# M220X.net
KiCad netlist of a schematic drawn in EAGLE
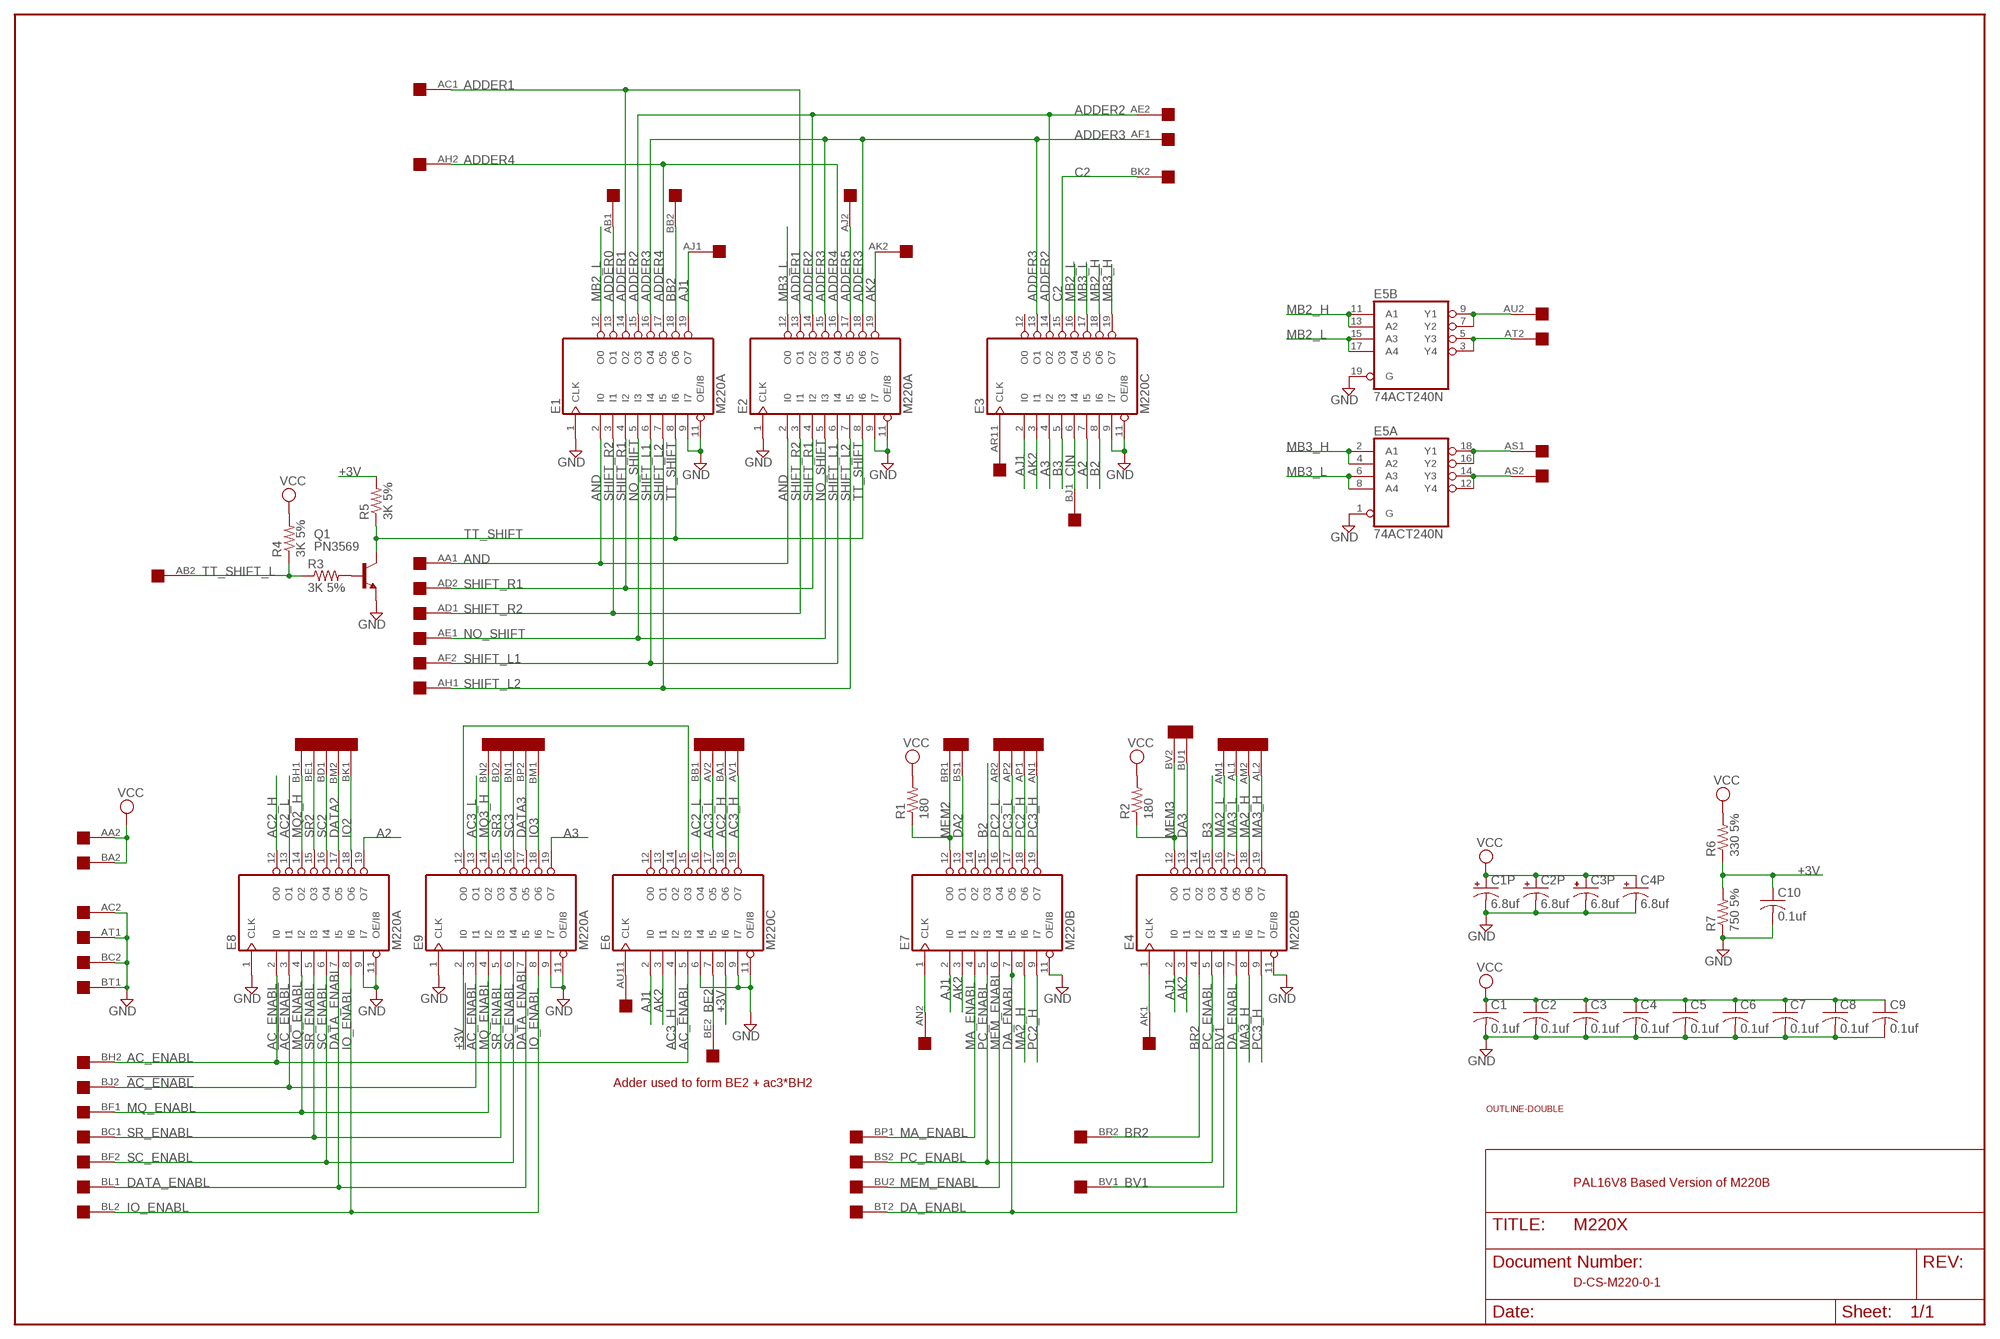
[diagram p0: schematic, sheet 1]

(export (version "E")
  (design (tool "Eeschema 10.0.6"))
  (components
    (comp (ref "C1")
      (value "0.1uf")
      (footprint "eagle-import:C050-025X075")
      (libsource (lib "eagle-import") (part "C-US050-025X075"))
    )
    (comp (ref "C1P")
      (value "6.8uf")
      (footprint "eagle-import:E15-5")
      (libsource (lib "eagle-import") (part "CPOL-USE15-5AXIAL"))
    )
    (comp (ref "C2")
      (value "0.1uf")
      (footprint "eagle-import:C050-025X075")
      (libsource (lib "eagle-import") (part "C-US050-025X075"))
    )
    (comp (ref "C2P")
      (value "6.8uf")
      (footprint "eagle-import:E15-5")
      (libsource (lib "eagle-import") (part "CPOL-USE15-5AXIAL"))
    )
    (comp (ref "C3")
      (value "0.1uf")
      (footprint "eagle-import:C050-025X075")
      (libsource (lib "eagle-import") (part "C-US050-025X075"))
    )
    (comp (ref "C3P")
      (value "6.8uf")
      (footprint "eagle-import:E15-5")
      (libsource (lib "eagle-import") (part "CPOL-USE15-5AXIAL"))
    )
    (comp (ref "C4")
      (value "0.1uf")
      (footprint "eagle-import:C050-025X075")
      (libsource (lib "eagle-import") (part "C-US050-025X075"))
    )
    (comp (ref "C4P")
      (value "6.8uf")
      (footprint "eagle-import:E15-5")
      (libsource (lib "eagle-import") (part "CPOL-USE15-5AXIAL"))
    )
    (comp (ref "C5")
      (value "0.1uf")
      (footprint "eagle-import:C050-025X075")
      (libsource (lib "eagle-import") (part "C-US050-025X075"))
    )
    (comp (ref "C6")
      (value "0.1uf")
      (footprint "eagle-import:C050-025X075")
      (libsource (lib "eagle-import") (part "C-US050-025X075"))
    )
    (comp (ref "C7")
      (value "0.1uf")
      (footprint "eagle-import:C050-025X075")
      (libsource (lib "eagle-import") (part "C-US050-025X075"))
    )
    (comp (ref "C8")
      (value "0.1uf")
      (footprint "eagle-import:C050-025X075")
      (libsource (lib "eagle-import") (part "C-US050-025X075"))
    )
    (comp (ref "C9")
      (value "0.1uf")
      (footprint "eagle-import:C050-025X075")
      (libsource (lib "eagle-import") (part "C-US050-025X075"))
    )
    (comp (ref "C10")
      (value "0.1uf")
      (footprint "eagle-import:C050-025X075")
      (libsource (lib "eagle-import") (part "C-US050-025X075"))
    )
    (comp (ref "E1")
      (value "M220A")
      (footprint "eagle-import:DIL20")
      (fields (field (name "MPN") "GAL16V8D-7LPN"))
      (libsource (lib "eagle-import") (part "16V8"))
    )
    (comp (ref "E2")
      (value "M220A")
      (footprint "eagle-import:DIL20")
      (fields (field (name "MPN") "GAL16V8D-7LPN"))
      (libsource (lib "eagle-import") (part "16V8"))
    )
    (comp (ref "E3")
      (value "M220C")
      (footprint "eagle-import:DIL20")
      (fields (field (name "MPN") "GAL16V8D-7LPN"))
      (libsource (lib "eagle-import") (part "16V8"))
    )
    (comp (ref "E4")
      (value "M220B")
      (footprint "eagle-import:DIL20")
      (fields (field (name "MPN") "GAL16V8D-7LPN"))
      (libsource (lib "eagle-import") (part "16V8"))
    )
    (comp (ref "E5")
      (value "74ACT240N")
      (footprint "eagle-import:DIL20")
      (libsource (lib "eagle-import") (part "74240NS"))
    )
    (comp (ref "E6")
      (value "M220C")
      (footprint "eagle-import:DIL20")
      (fields (field (name "MPN") "GAL16V8D-7LPN"))
      (libsource (lib "eagle-import") (part "16V8"))
    )
    (comp (ref "E7")
      (value "M220B")
      (footprint "eagle-import:DIL20")
      (fields (field (name "MPN") "GAL16V8D-7LPN"))
      (libsource (lib "eagle-import") (part "16V8"))
    )
    (comp (ref "E8")
      (value "M220A")
      (footprint "eagle-import:DIL20")
      (fields (field (name "MPN") "GAL16V8D-7LPN"))
      (libsource (lib "eagle-import") (part "16V8"))
    )
    (comp (ref "E9")
      (value "M220A")
      (footprint "eagle-import:DIL20")
      (fields (field (name "MPN") "GAL16V8D-7LPN"))
      (libsource (lib "eagle-import") (part "16V8"))
    )
    (comp (ref "Q1")
      (value "PN3569")
      (footprint "eagle-import:TO5")
      (libsource (lib "eagle-import") (part "2N2102"))
    )
    (comp (ref "R1")
      (value "180")
      (footprint "eagle-import:0207_10")
      (libsource (lib "eagle-import") (part "R-US_0207/10"))
    )
    (comp (ref "R2")
      (value "180")
      (footprint "eagle-import:0207_10")
      (libsource (lib "eagle-import") (part "R-US_0207/10"))
    )
    (comp (ref "R3")
      (value "3K 5%")
      (footprint "eagle-import:0207_10")
      (libsource (lib "eagle-import") (part "R-US_0207/10"))
    )
    (comp (ref "R4")
      (value "3K 5%")
      (footprint "eagle-import:0207_10")
      (libsource (lib "eagle-import") (part "R-US_0207/10"))
    )
    (comp (ref "R5")
      (value "3K 5%")
      (footprint "eagle-import:0207_10")
      (libsource (lib "eagle-import") (part "R-US_0207/10"))
    )
    (comp (ref "R6")
      (value "330 5%")
      (footprint "eagle-import:0207_10")
      (libsource (lib "eagle-import") (part "R-US_0207/10"))
    )
    (comp (ref "R7")
      (value "750 5%")
      (footprint "eagle-import:0207_10")
      (libsource (lib "eagle-import") (part "R-US_0207/10"))
    )
    (comp (ref "U$1")
      (value "DOUBLE")
      (footprint "eagle-import:EDGE-CON4")
      (libsource (lib "eagle-import") (part "DOUBLE"))
    )
    (comp (ref "U$2")
      (value "OUTLINE-DOUBLE")
      (footprint "eagle-import:DOUBLE")
      (libsource (lib "eagle-import") (part "OUTLINE-DOUBLE"))
    )
  )
  (nets
    (net (code "1") (name "/+3V") (class "Default")
      (node (ref "C10") (pin "1") (pinfunction "1_1") (pintype "passive"))
      (node (ref "E6") (pin "8") (pinfunction "I6_8") (pintype "input"))
      (node (ref "E9") (pin "2") (pinfunction "I0_2") (pintype "input"))
      (node (ref "R5") (pin "2") (pinfunction "2_2") (pintype "passive"))
      (node (ref "R6") (pin "1") (pinfunction "1_1") (pintype "passive"))
      (node (ref "R7") (pin "2") (pinfunction "2_2") (pintype "passive"))
    )
    (net (code "2") (name "/A2") (class "Default")
      (node (ref "E3") (pin "7") (pinfunction "I5_7") (pintype "input"))
      (node (ref "E8") (pin "19") (pinfunction "O7_19") (pintype "bidirectional"))
    )
    (net (code "3") (name "/A3") (class "Default")
      (node (ref "E3") (pin "4") (pinfunction "I2_4") (pintype "input"))
      (node (ref "E9") (pin "19") (pinfunction "O7_19") (pintype "bidirectional"))
    )
    (net (code "4") (name "/AC2_H") (class "Default")
      (node (ref "E6") (pin "18") (pinfunction "O6_18") (pintype "bidirectional"))
      (node (ref "E8") (pin "12") (pinfunction "O0_12") (pintype "bidirectional"))
      (node (ref "U$1") (pin "BA1") (pinfunction "1_BA1") (pintype "bidirectional"))
    )
    (net (code "5") (name "/AC2_L") (class "Default")
      (node (ref "E6") (pin "16") (pinfunction "O4_16") (pintype "bidirectional"))
      (node (ref "E8") (pin "13") (pinfunction "O1_13") (pintype "bidirectional"))
      (node (ref "U$1") (pin "BB1") (pinfunction "1_BB1") (pintype "bidirectional"))
    )
    (net (code "6") (name "/AC3_H") (class "Default")
      (node (ref "E6") (pin "19") (pinfunction "O7_19") (pintype "bidirectional"))
      (node (ref "E6") (pin "4") (pinfunction "I2_4") (pintype "input"))
      (node (ref "U$1") (pin "AV1") (pinfunction "1_AV1") (pintype "bidirectional"))
    )
    (net (code "7") (name "/AC3_L") (class "Default")
      (node (ref "E6") (pin "17") (pinfunction "O5_17") (pintype "bidirectional"))
      (node (ref "E9") (pin "13") (pinfunction "O1_13") (pintype "bidirectional"))
      (node (ref "U$1") (pin "AV2") (pinfunction "1_AV2") (pintype "bidirectional"))
    )
    (net (code "8") (name "/AC_ENABL") (class "Default")
      (node (ref "E6") (pin "5") (pinfunction "I3_5") (pintype "input"))
      (node (ref "E8") (pin "2") (pinfunction "I0_2") (pintype "input"))
      (node (ref "U$1") (pin "BH2") (pinfunction "1_BH2") (pintype "bidirectional"))
    )
    (net (code "9") (name "/ADDER0") (class "Default")
      (node (ref "E1") (pin "13") (pinfunction "O1_13") (pintype "bidirectional"))
      (node (ref "U$1") (pin "AB1") (pinfunction "1_AB1") (pintype "bidirectional"))
    )
    (net (code "10") (name "/ADDER1") (class "Default")
      (node (ref "E1") (pin "14") (pinfunction "O2_14") (pintype "bidirectional"))
      (node (ref "E2") (pin "13") (pinfunction "O1_13") (pintype "bidirectional"))
      (node (ref "U$1") (pin "AC1") (pinfunction "1_AC1") (pintype "bidirectional"))
    )
    (net (code "11") (name "/ADDER2") (class "Default")
      (node (ref "E1") (pin "15") (pinfunction "O3_15") (pintype "bidirectional"))
      (node (ref "E2") (pin "14") (pinfunction "O2_14") (pintype "bidirectional"))
      (node (ref "E3") (pin "14") (pinfunction "O2_14") (pintype "bidirectional"))
      (node (ref "U$1") (pin "AE2") (pinfunction "1_AE2") (pintype "bidirectional"))
    )
    (net (code "12") (name "/ADDER3") (class "Default")
      (node (ref "E1") (pin "16") (pinfunction "O4_16") (pintype "bidirectional"))
      (node (ref "E2") (pin "15") (pinfunction "O3_15") (pintype "bidirectional"))
      (node (ref "E2") (pin "18") (pinfunction "O6_18") (pintype "bidirectional"))
      (node (ref "E3") (pin "13") (pinfunction "O1_13") (pintype "bidirectional"))
      (node (ref "U$1") (pin "AF1") (pinfunction "1_AF1") (pintype "bidirectional"))
    )
    (net (code "13") (name "/ADDER4") (class "Default")
      (node (ref "E1") (pin "17") (pinfunction "O5_17") (pintype "bidirectional"))
      (node (ref "E2") (pin "16") (pinfunction "O4_16") (pintype "bidirectional"))
      (node (ref "U$1") (pin "AH2") (pinfunction "1_AH2") (pintype "bidirectional"))
    )
    (net (code "14") (name "/ADDER5") (class "Default")
      (node (ref "E2") (pin "17") (pinfunction "O5_17") (pintype "bidirectional"))
      (node (ref "U$1") (pin "AJ2") (pinfunction "1_AJ2") (pintype "bidirectional"))
    )
    (net (code "15") (name "/AJ1") (class "Default")
      (node (ref "E1") (pin "19") (pinfunction "O7_19") (pintype "bidirectional"))
      (node (ref "E3") (pin "2") (pinfunction "I0_2") (pintype "input"))
      (node (ref "E4") (pin "2") (pinfunction "I0_2") (pintype "input"))
      (node (ref "E6") (pin "2") (pinfunction "I0_2") (pintype "input"))
      (node (ref "E7") (pin "2") (pinfunction "I0_2") (pintype "input"))
      (node (ref "U$1") (pin "AJ1") (pinfunction "1_AJ1") (pintype "bidirectional"))
    )
    (net (code "16") (name "/AK2") (class "Default")
      (node (ref "E2") (pin "19") (pinfunction "O7_19") (pintype "bidirectional"))
      (node (ref "E3") (pin "3") (pinfunction "I1_3") (pintype "input"))
      (node (ref "E4") (pin "3") (pinfunction "I1_3") (pintype "input"))
      (node (ref "E6") (pin "3") (pinfunction "I1_3") (pintype "input"))
      (node (ref "E7") (pin "3") (pinfunction "I1_3") (pintype "input"))
      (node (ref "U$1") (pin "AK2") (pinfunction "1_AK2") (pintype "bidirectional"))
    )
    (net (code "17") (name "/AND") (class "Default")
      (node (ref "E1") (pin "2") (pinfunction "I0_2") (pintype "input"))
      (node (ref "E2") (pin "2") (pinfunction "I0_2") (pintype "input"))
      (node (ref "U$1") (pin "AA1") (pinfunction "1_AA1") (pintype "bidirectional"))
    )
    (net (code "18") (name "/B2") (class "Default")
      (node (ref "E3") (pin "8") (pinfunction "I6_8") (pintype "input"))
      (node (ref "E7") (pin "15") (pinfunction "O3_15") (pintype "bidirectional"))
    )
    (net (code "19") (name "/B3") (class "Default")
      (node (ref "E3") (pin "5") (pinfunction "I3_5") (pintype "input"))
      (node (ref "E4") (pin "15") (pinfunction "O3_15") (pintype "bidirectional"))
    )
    (net (code "20") (name "/BB2") (class "Default")
      (node (ref "E1") (pin "18") (pinfunction "O6_18") (pintype "bidirectional"))
      (node (ref "U$1") (pin "BB2") (pinfunction "1_BB2") (pintype "bidirectional"))
    )
    (net (code "21") (name "/BE2") (class "Default")
      (node (ref "E6") (pin "7") (pinfunction "I5_7") (pintype "input"))
      (node (ref "U$1") (pin "BE2") (pinfunction "1_BE2") (pintype "bidirectional"))
    )
    (net (code "22") (name "/BR2") (class "Default")
      (node (ref "E4") (pin "4") (pinfunction "I2_4") (pintype "input"))
      (node (ref "U$1") (pin "BR2") (pinfunction "1_BR2") (pintype "bidirectional"))
    )
    (net (code "23") (name "/BV1") (class "Default")
      (node (ref "E4") (pin "6") (pinfunction "I4_6") (pintype "input"))
      (node (ref "U$1") (pin "BV1") (pinfunction "1_BV1") (pintype "bidirectional"))
    )
    (net (code "24") (name "/C2") (class "Default")
      (node (ref "E3") (pin "15") (pinfunction "O3_15") (pintype "bidirectional"))
      (node (ref "U$1") (pin "BK2") (pinfunction "1_BK2") (pintype "bidirectional"))
    )
    (net (code "25") (name "/CIN") (class "Default")
      (node (ref "E3") (pin "6") (pinfunction "I4_6") (pintype "input"))
      (node (ref "U$1") (pin "BJ1") (pinfunction "1_BJ1") (pintype "bidirectional"))
    )
    (net (code "26") (name "/DA2") (class "Default")
      (node (ref "E7") (pin "13") (pinfunction "O1_13") (pintype "bidirectional"))
      (node (ref "U$1") (pin "BS1") (pinfunction "1_BS1") (pintype "bidirectional"))
    )
    (net (code "27") (name "/DA3") (class "Default")
      (node (ref "E4") (pin "13") (pinfunction "O1_13") (pintype "bidirectional"))
      (node (ref "U$1") (pin "BU1") (pinfunction "1_BU1") (pintype "bidirectional"))
    )
    (net (code "28") (name "/DATA2") (class "Default")
      (node (ref "E8") (pin "17") (pinfunction "O5_17") (pintype "bidirectional"))
      (node (ref "U$1") (pin "BM2") (pinfunction "1_BM2") (pintype "bidirectional"))
    )
    (net (code "29") (name "/DATA3") (class "Default")
      (node (ref "E9") (pin "17") (pinfunction "O5_17") (pintype "bidirectional"))
      (node (ref "U$1") (pin "BP2") (pinfunction "1_BP2") (pintype "bidirectional"))
    )
    (net (code "30") (name "/DATA_ENABL") (class "Default")
      (node (ref "E8") (pin "7") (pinfunction "I5_7") (pintype "input"))
      (node (ref "E9") (pin "7") (pinfunction "I5_7") (pintype "input"))
      (node (ref "U$1") (pin "BL1") (pinfunction "1_BL1") (pintype "bidirectional"))
    )
    (net (code "31") (name "/DA_ENABL") (class "Default")
      (node (ref "E4") (pin "7") (pinfunction "I5_7") (pintype "input"))
      (node (ref "E7") (pin "7") (pinfunction "I5_7") (pintype "input"))
      (node (ref "U$1") (pin "BT2") (pinfunction "1_BT2") (pintype "bidirectional"))
    )
    (net (code "32") (name "/IO2") (class "Default")
      (node (ref "E8") (pin "18") (pinfunction "O6_18") (pintype "bidirectional"))
      (node (ref "U$1") (pin "BK1") (pinfunction "1_BK1") (pintype "bidirectional"))
    )
    (net (code "33") (name "/IO3") (class "Default")
      (node (ref "E9") (pin "18") (pinfunction "O6_18") (pintype "bidirectional"))
      (node (ref "U$1") (pin "BM1") (pinfunction "1_BM1") (pintype "bidirectional"))
    )
    (net (code "34") (name "/IO_ENABL") (class "Default")
      (node (ref "E8") (pin "8") (pinfunction "I6_8") (pintype "input"))
      (node (ref "E9") (pin "8") (pinfunction "I6_8") (pintype "input"))
      (node (ref "U$1") (pin "BL2") (pinfunction "1_BL2") (pintype "bidirectional"))
    )
    (net (code "35") (name "/MA2_H") (class "Default")
      (node (ref "E4") (pin "18") (pinfunction "O6_18") (pintype "bidirectional"))
      (node (ref "E7") (pin "8") (pinfunction "I6_8") (pintype "input"))
      (node (ref "U$1") (pin "AM2") (pinfunction "1_AM2") (pintype "bidirectional"))
    )
    (net (code "36") (name "/MA2_L") (class "Default")
      (node (ref "E4") (pin "16") (pinfunction "O4_16") (pintype "bidirectional"))
      (node (ref "U$1") (pin "AM1") (pinfunction "1_AM1") (pintype "bidirectional"))
    )
    (net (code "37") (name "/MA3_H") (class "Default")
      (node (ref "E4") (pin "19") (pinfunction "O7_19") (pintype "bidirectional"))
      (node (ref "E4") (pin "8") (pinfunction "I6_8") (pintype "input"))
      (node (ref "U$1") (pin "AL2") (pinfunction "1_AL2") (pintype "bidirectional"))
    )
    (net (code "38") (name "/MA3_L") (class "Default")
      (node (ref "E4") (pin "17") (pinfunction "O5_17") (pintype "bidirectional"))
      (node (ref "U$1") (pin "AL1") (pinfunction "1_AL1") (pintype "bidirectional"))
    )
    (net (code "39") (name "/MA_ENABL") (class "Default")
      (node (ref "E7") (pin "4") (pinfunction "I2_4") (pintype "input"))
      (node (ref "U$1") (pin "BP1") (pinfunction "1_BP1") (pintype "bidirectional"))
    )
    (net (code "40") (name "/MB2_H") (class "Default")
      (node (ref "E3") (pin "18") (pinfunction "O6_18") (pintype "bidirectional"))
      (node (ref "E5") (pin "11") (pinfunction "A1_11") (pintype "input"))
      (node (ref "E5") (pin "13") (pinfunction "A2_13") (pintype "input"))
    )
    (net (code "41") (name "/MB2_L") (class "Default")
      (node (ref "E1") (pin "12") (pinfunction "O0_12") (pintype "bidirectional"))
      (node (ref "E3") (pin "16") (pinfunction "O4_16") (pintype "bidirectional"))
      (node (ref "E5") (pin "15") (pinfunction "A3_15") (pintype "input"))
      (node (ref "E5") (pin "17") (pinfunction "A4_17") (pintype "input"))
    )
    (net (code "42") (name "/MB3_H") (class "Default")
      (node (ref "E3") (pin "19") (pinfunction "O7_19") (pintype "bidirectional"))
      (node (ref "E5") (pin "2") (pinfunction "A1_2") (pintype "input"))
      (node (ref "E5") (pin "4") (pinfunction "A2_4") (pintype "input"))
    )
    (net (code "43") (name "/MB3_L") (class "Default")
      (node (ref "E2") (pin "12") (pinfunction "O0_12") (pintype "bidirectional"))
      (node (ref "E3") (pin "17") (pinfunction "O5_17") (pintype "bidirectional"))
      (node (ref "E5") (pin "6") (pinfunction "A3_6") (pintype "input"))
      (node (ref "E5") (pin "8") (pinfunction "A4_8") (pintype "input"))
    )
    (net (code "44") (name "/MEM2") (class "Default")
      (node (ref "E7") (pin "12") (pinfunction "O0_12") (pintype "bidirectional"))
      (node (ref "R1") (pin "1") (pinfunction "1_1") (pintype "passive"))
      (node (ref "U$1") (pin "BR1") (pinfunction "1_BR1") (pintype "bidirectional"))
    )
    (net (code "45") (name "/MEM3") (class "Default")
      (node (ref "E4") (pin "12") (pinfunction "O0_12") (pintype "bidirectional"))
      (node (ref "R2") (pin "1") (pinfunction "1_1") (pintype "passive"))
      (node (ref "U$1") (pin "BV2") (pinfunction "1_BV2") (pintype "bidirectional"))
    )
    (net (code "46") (name "/MEM_ENABL") (class "Default")
      (node (ref "E7") (pin "6") (pinfunction "I4_6") (pintype "input"))
      (node (ref "U$1") (pin "BU2") (pinfunction "1_BU2") (pintype "bidirectional"))
    )
    (net (code "47") (name "/MQ2_H") (class "Default")
      (node (ref "E8") (pin "14") (pinfunction "O2_14") (pintype "bidirectional"))
      (node (ref "U$1") (pin "BH1") (pinfunction "1_BH1") (pintype "bidirectional"))
    )
    (net (code "48") (name "/MQ3_H") (class "Default")
      (node (ref "E9") (pin "14") (pinfunction "O2_14") (pintype "bidirectional"))
      (node (ref "U$1") (pin "BN2") (pinfunction "1_BN2") (pintype "bidirectional"))
    )
    (net (code "49") (name "/MQ_ENABL") (class "Default")
      (node (ref "E8") (pin "4") (pinfunction "I2_4") (pintype "input"))
      (node (ref "E9") (pin "4") (pinfunction "I2_4") (pintype "input"))
      (node (ref "U$1") (pin "BF1") (pinfunction "1_BF1") (pintype "bidirectional"))
    )
    (net (code "50") (name "/NO_SHIFT") (class "Default")
      (node (ref "E1") (pin "5") (pinfunction "I3_5") (pintype "input"))
      (node (ref "E2") (pin "5") (pinfunction "I3_5") (pintype "input"))
      (node (ref "U$1") (pin "AE1") (pinfunction "1_AE1") (pintype "bidirectional"))
    )
    (net (code "51") (name "/PC2_H") (class "Default")
      (node (ref "E7") (pin "18") (pinfunction "O6_18") (pintype "bidirectional"))
      (node (ref "E7") (pin "9") (pinfunction "I7_9") (pintype "input"))
      (node (ref "U$1") (pin "AP1") (pinfunction "1_AP1") (pintype "bidirectional"))
    )
    (net (code "52") (name "/PC2_L") (class "Default")
      (node (ref "E7") (pin "16") (pinfunction "O4_16") (pintype "bidirectional"))
      (node (ref "U$1") (pin "AR2") (pinfunction "1_AR2") (pintype "bidirectional"))
    )
    (net (code "53") (name "/PC3_H") (class "Default")
      (node (ref "E4") (pin "9") (pinfunction "I7_9") (pintype "input"))
      (node (ref "E7") (pin "19") (pinfunction "O7_19") (pintype "bidirectional"))
      (node (ref "U$1") (pin "AN1") (pinfunction "1_AN1") (pintype "bidirectional"))
    )
    (net (code "54") (name "/PC3_L") (class "Default")
      (node (ref "E7") (pin "17") (pinfunction "O5_17") (pintype "bidirectional"))
      (node (ref "U$1") (pin "AP2") (pinfunction "1_AP2") (pintype "bidirectional"))
    )
    (net (code "55") (name "/PC_ENABL") (class "Default")
      (node (ref "E4") (pin "5") (pinfunction "I3_5") (pintype "input"))
      (node (ref "E7") (pin "5") (pinfunction "I3_5") (pintype "input"))
      (node (ref "U$1") (pin "BS2") (pinfunction "1_BS2") (pintype "bidirectional"))
    )
    (net (code "56") (name "/SC2") (class "Default")
      (node (ref "E8") (pin "16") (pinfunction "O4_16") (pintype "bidirectional"))
      (node (ref "U$1") (pin "BD1") (pinfunction "1_BD1") (pintype "bidirectional"))
    )
    (net (code "57") (name "/SC3") (class "Default")
      (node (ref "E9") (pin "16") (pinfunction "O4_16") (pintype "bidirectional"))
      (node (ref "U$1") (pin "BN1") (pinfunction "1_BN1") (pintype "bidirectional"))
    )
    (net (code "58") (name "/SC_ENABL") (class "Default")
      (node (ref "E8") (pin "6") (pinfunction "I4_6") (pintype "input"))
      (node (ref "E9") (pin "6") (pinfunction "I4_6") (pintype "input"))
      (node (ref "U$1") (pin "BF2") (pinfunction "1_BF2") (pintype "bidirectional"))
    )
    (net (code "59") (name "/SHIFT_L1") (class "Default")
      (node (ref "E1") (pin "6") (pinfunction "I4_6") (pintype "input"))
      (node (ref "E2") (pin "6") (pinfunction "I4_6") (pintype "input"))
      (node (ref "U$1") (pin "AF2") (pinfunction "1_AF2") (pintype "bidirectional"))
    )
    (net (code "60") (name "/SHIFT_L2") (class "Default")
      (node (ref "E1") (pin "7") (pinfunction "I5_7") (pintype "input"))
      (node (ref "E2") (pin "7") (pinfunction "I5_7") (pintype "input"))
      (node (ref "U$1") (pin "AH1") (pinfunction "1_AH1") (pintype "bidirectional"))
    )
    (net (code "61") (name "/SHIFT_R1") (class "Default")
      (node (ref "E1") (pin "4") (pinfunction "I2_4") (pintype "input"))
      (node (ref "E2") (pin "4") (pinfunction "I2_4") (pintype "input"))
      (node (ref "U$1") (pin "AD2") (pinfunction "1_AD2") (pintype "bidirectional"))
    )
    (net (code "62") (name "/SHIFT_R2") (class "Default")
      (node (ref "E1") (pin "3") (pinfunction "I1_3") (pintype "input"))
      (node (ref "E2") (pin "3") (pinfunction "I1_3") (pintype "input"))
      (node (ref "U$1") (pin "AD1") (pinfunction "1_AD1") (pintype "bidirectional"))
    )
    (net (code "63") (name "/SR2") (class "Default")
      (node (ref "E8") (pin "15") (pinfunction "O3_15") (pintype "bidirectional"))
      (node (ref "U$1") (pin "BE1") (pinfunction "1_BE1") (pintype "bidirectional"))
    )
    (net (code "64") (name "/SR3") (class "Default")
      (node (ref "E9") (pin "15") (pinfunction "O3_15") (pintype "bidirectional"))
      (node (ref "U$1") (pin "BD2") (pinfunction "1_BD2") (pintype "bidirectional"))
    )
    (net (code "65") (name "/SR_ENABL") (class "Default")
      (node (ref "E8") (pin "5") (pinfunction "I3_5") (pintype "input"))
      (node (ref "E9") (pin "5") (pinfunction "I3_5") (pintype "input"))
      (node (ref "U$1") (pin "BC1") (pinfunction "1_BC1") (pintype "bidirectional"))
    )
    (net (code "66") (name "/TT_SHIFT") (class "Default")
      (node (ref "E1") (pin "8") (pinfunction "I6_8") (pintype "input"))
      (node (ref "E2") (pin "8") (pinfunction "I6_8") (pintype "input"))
      (node (ref "Q1") (pin "3") (pinfunction "C_3") (pintype "passive"))
      (node (ref "R5") (pin "1") (pinfunction "1_1") (pintype "passive"))
    )
    (net (code "67") (name "/TT_SHIFT_L") (class "Default")
      (node (ref "R3") (pin "1") (pinfunction "1_1") (pintype "passive"))
      (node (ref "R4") (pin "1") (pinfunction "1_1") (pintype "passive"))
      (node (ref "U$1") (pin "AB2") (pinfunction "1_AB2") (pintype "bidirectional"))
    )
    (net (code "68") (name "/~{AC_ENABL}") (class "Default")
      (node (ref "E8") (pin "3") (pinfunction "I1_3") (pintype "input"))
      (node (ref "E9") (pin "3") (pinfunction "I1_3") (pintype "input"))
      (node (ref "U$1") (pin "BJ2") (pinfunction "1_BJ2") (pintype "bidirectional"))
    )
    (net (code "69") (name "GND") (class "Default")
      (node (ref "C1") (pin "2") (pinfunction "2_2") (pintype "passive"))
      (node (ref "C10") (pin "2") (pinfunction "2_2") (pintype "passive"))
      (node (ref "C1P") (pin "-") (pinfunction "-_-") (pintype "passive"))
      (node (ref "C2") (pin "2") (pinfunction "2_2") (pintype "passive"))
      (node (ref "C2P") (pin "-") (pinfunction "-_-") (pintype "passive"))
      (node (ref "C3") (pin "2") (pinfunction "2_2") (pintype "passive"))
      (node (ref "C3P") (pin "-") (pinfunction "-_-") (pintype "passive"))
      (node (ref "C4") (pin "2") (pinfunction "2_2") (pintype "passive"))
      (node (ref "C4P") (pin "-") (pinfunction "-_-") (pintype "passive"))
      (node (ref "C5") (pin "2") (pinfunction "2_2") (pintype "passive"))
      (node (ref "C6") (pin "2") (pinfunction "2_2") (pintype "passive"))
      (node (ref "C7") (pin "2") (pinfunction "2_2") (pintype "passive"))
      (node (ref "C8") (pin "2") (pinfunction "2_2") (pintype "passive"))
      (node (ref "C9") (pin "2") (pinfunction "2_2") (pintype "passive"))
      (node (ref "E1") (pin "1") (pinfunction "CLK_1") (pintype "input"))
      (node (ref "E1") (pin "11") (pinfunction "OE/I8_11") (pintype "input"))
      (node (ref "E1") (pin "9") (pinfunction "I7_9") (pintype "input"))
      (node (ref "E2") (pin "1") (pinfunction "CLK_1") (pintype "input"))
      (node (ref "E2") (pin "11") (pinfunction "OE/I8_11") (pintype "input"))
      (node (ref "E2") (pin "9") (pinfunction "I7_9") (pintype "input"))
      (node (ref "E3") (pin "11") (pinfunction "OE/I8_11") (pintype "input"))
      (node (ref "E3") (pin "9") (pinfunction "I7_9") (pintype "input"))
      (node (ref "E4") (pin "11") (pinfunction "OE/I8_11") (pintype "input"))
      (node (ref "E5") (pin "1") (pinfunction "G_1") (pintype "input"))
      (node (ref "E5") (pin "19") (pinfunction "G_19") (pintype "input"))
      (node (ref "E6") (pin "11") (pinfunction "OE/I8_11") (pintype "input"))
      (node (ref "E6") (pin "6") (pinfunction "I4_6") (pintype "input"))
      (node (ref "E6") (pin "9") (pinfunction "I7_9") (pintype "input"))
      (node (ref "E7") (pin "11") (pinfunction "OE/I8_11") (pintype "input"))
      (node (ref "E8") (pin "1") (pinfunction "CLK_1") (pintype "input"))
      (node (ref "E8") (pin "11") (pinfunction "OE/I8_11") (pintype "input"))
      (node (ref "E8") (pin "9") (pinfunction "I7_9") (pintype "input"))
      (node (ref "E9") (pin "1") (pinfunction "CLK_1") (pintype "input"))
      (node (ref "E9") (pin "11") (pinfunction "OE/I8_11") (pintype "input"))
      (node (ref "E9") (pin "9") (pinfunction "I7_9") (pintype "input"))
      (node (ref "Q1") (pin "1") (pinfunction "E_1") (pintype "passive"))
      (node (ref "R7") (pin "1") (pinfunction "1_1") (pintype "passive"))
      (node (ref "U$1") (pin "AC2") (pinfunction "1_AC2") (pintype "bidirectional"))
      (node (ref "U$1") (pin "AT1") (pinfunction "1_AT1") (pintype "bidirectional"))
      (node (ref "U$1") (pin "BC2") (pinfunction "1_BC2") (pintype "bidirectional"))
      (node (ref "U$1") (pin "BT1") (pinfunction "1_BT1") (pintype "bidirectional"))
    )
    (net (code "70") (name "Net-(E3A-CLK)") (class "Default")
      (node (ref "E3") (pin "1") (pinfunction "CLK_1") (pintype "input"))
      (node (ref "U$1") (pin "AR1") (pinfunction "1_AR1") (pintype "bidirectional"))
    )
    (net (code "71") (name "Net-(E4A-CLK)") (class "Default")
      (node (ref "E4") (pin "1") (pinfunction "CLK_1") (pintype "input"))
      (node (ref "U$1") (pin "AK1") (pinfunction "1_AK1") (pintype "bidirectional"))
    )
    (net (code "72") (name "Net-(E5A-Y1)") (class "Default")
      (node (ref "E5") (pin "16") (pinfunction "Y2_16") (pintype "tri_state"))
      (node (ref "E5") (pin "18") (pinfunction "Y1_18") (pintype "tri_state"))
      (node (ref "U$1") (pin "AS1") (pinfunction "1_AS1") (pintype "bidirectional"))
    )
    (net (code "73") (name "Net-(E5A-Y3)") (class "Default")
      (node (ref "E5") (pin "12") (pinfunction "Y4_12") (pintype "tri_state"))
      (node (ref "E5") (pin "14") (pinfunction "Y3_14") (pintype "tri_state"))
      (node (ref "U$1") (pin "AS2") (pinfunction "1_AS2") (pintype "bidirectional"))
    )
    (net (code "74") (name "Net-(E5B-Y1)") (class "Default")
      (node (ref "E5") (pin "7") (pinfunction "Y2_7") (pintype "tri_state"))
      (node (ref "E5") (pin "9") (pinfunction "Y1_9") (pintype "tri_state"))
      (node (ref "U$1") (pin "AU2") (pinfunction "1_AU2") (pintype "bidirectional"))
    )
    (net (code "75") (name "Net-(E5B-Y3)") (class "Default")
      (node (ref "E5") (pin "3") (pinfunction "Y4_3") (pintype "tri_state"))
      (node (ref "E5") (pin "5") (pinfunction "Y3_5") (pintype "tri_state"))
      (node (ref "U$1") (pin "AT2") (pinfunction "1_AT2") (pintype "bidirectional"))
    )
    (net (code "76") (name "Net-(E6A-CLK)") (class "Default")
      (node (ref "E6") (pin "1") (pinfunction "CLK_1") (pintype "input"))
      (node (ref "U$1") (pin "AU1") (pinfunction "1_AU1") (pintype "bidirectional"))
    )
    (net (code "77") (name "Net-(E6A-O3)") (class "Default")
      (node (ref "E6") (pin "15") (pinfunction "O3_15") (pintype "bidirectional"))
      (node (ref "E9") (pin "12") (pinfunction "O0_12") (pintype "bidirectional"))
    )
    (net (code "78") (name "Net-(E7A-CLK)") (class "Default")
      (node (ref "E7") (pin "1") (pinfunction "CLK_1") (pintype "input"))
      (node (ref "U$1") (pin "AN2") (pinfunction "1_AN2") (pintype "bidirectional"))
    )
    (net (code "79") (name "Net-(Q1-B)") (class "Default")
      (node (ref "Q1") (pin "2") (pinfunction "B_2") (pintype "passive"))
      (node (ref "R3") (pin "2") (pinfunction "2_2") (pintype "passive"))
    )
    (net (code "80") (name "VCC") (class "Default")
      (node (ref "C1") (pin "1") (pinfunction "1_1") (pintype "passive"))
      (node (ref "C1P") (pin "+") (pinfunction "+_+") (pintype "passive"))
      (node (ref "C2") (pin "1") (pinfunction "1_1") (pintype "passive"))
      (node (ref "C2P") (pin "+") (pinfunction "+_+") (pintype "passive"))
      (node (ref "C3") (pin "1") (pinfunction "1_1") (pintype "passive"))
      (node (ref "C3P") (pin "+") (pinfunction "+_+") (pintype "passive"))
      (node (ref "C4") (pin "1") (pinfunction "1_1") (pintype "passive"))
      (node (ref "C4P") (pin "+") (pinfunction "+_+") (pintype "passive"))
      (node (ref "C5") (pin "1") (pinfunction "1_1") (pintype "passive"))
      (node (ref "C6") (pin "1") (pinfunction "1_1") (pintype "passive"))
      (node (ref "C7") (pin "1") (pinfunction "1_1") (pintype "passive"))
      (node (ref "C8") (pin "1") (pinfunction "1_1") (pintype "passive"))
      (node (ref "C9") (pin "1") (pinfunction "1_1") (pintype "passive"))
      (node (ref "R1") (pin "2") (pinfunction "2_2") (pintype "passive"))
      (node (ref "R2") (pin "2") (pinfunction "2_2") (pintype "passive"))
      (node (ref "R4") (pin "2") (pinfunction "2_2") (pintype "passive"))
      (node (ref "R6") (pin "2") (pinfunction "2_2") (pintype "passive"))
      (node (ref "U$1") (pin "AA2") (pinfunction "1_AA2") (pintype "bidirectional"))
      (node (ref "U$1") (pin "BA2") (pinfunction "1_BA2") (pintype "bidirectional"))
    )
    (net (code "81") (name "unconnected-(E3A-O0-Pad12)") (class "Default")
      (node (ref "E3") (pin "12") (pinfunction "O0_12") (pintype "bidirectional"))
    )
    (net (code "82") (name "unconnected-(E4A-O2-Pad14)") (class "Default")
      (node (ref "E4") (pin "14") (pinfunction "O2_14") (pintype "bidirectional"))
    )
    (net (code "83") (name "unconnected-(E6A-O0-Pad12)") (class "Default")
      (node (ref "E6") (pin "12") (pinfunction "O0_12") (pintype "bidirectional"))
    )
    (net (code "84") (name "unconnected-(E6A-O1-Pad13)") (class "Default")
      (node (ref "E6") (pin "13") (pinfunction "O1_13") (pintype "bidirectional"))
    )
    (net (code "85") (name "unconnected-(E6A-O2-Pad14)") (class "Default")
      (node (ref "E6") (pin "14") (pinfunction "O2_14") (pintype "bidirectional"))
    )
    (net (code "86") (name "unconnected-(E7A-O2-Pad14)") (class "Default")
      (node (ref "E7") (pin "14") (pinfunction "O2_14") (pintype "bidirectional"))
    )
  )
)
